# 4_digit_7seg_driver.net
KiCad netlist of a schematic drawn in EAGLE
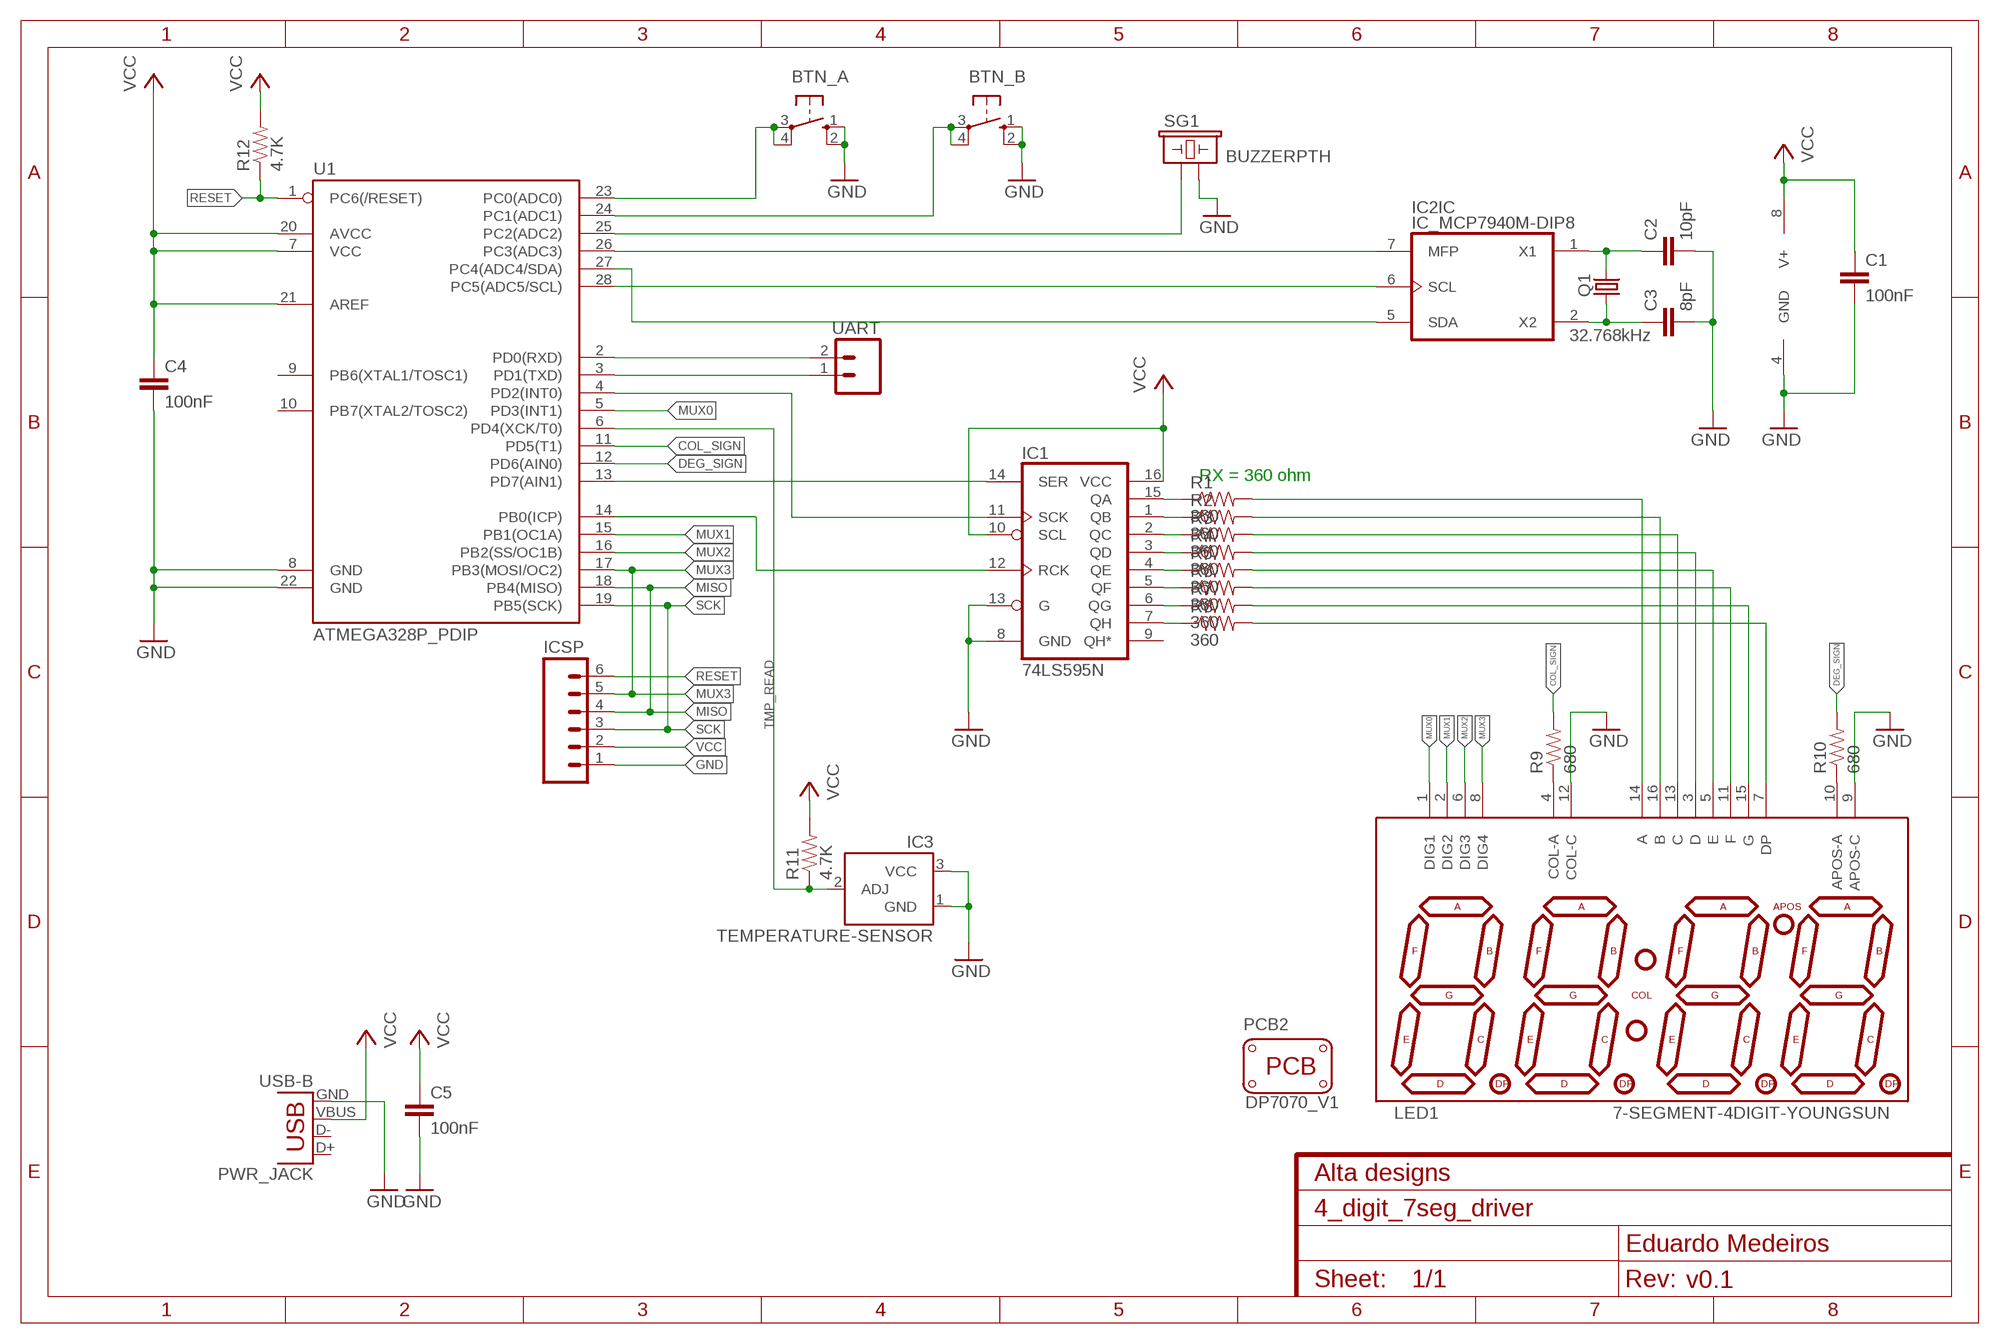
[diagram p0: schematic, sheet 1]

(export (version "E")
  (design (tool "Eeschema 10.0.6"))
  (components
    (comp (ref "BTN_A")
      (value "40-XX")
      (footprint "eagle-import:B3F-40XX")
      (fields (field (name "MF") "OMRON COMPONENTS USA") (field (name "MPN") "B3F-4000"))
      (libsource (lib "eagle-import") (part "40-XX"))
    )
    (comp (ref "BTN_B")
      (value "40-XX")
      (footprint "eagle-import:B3F-40XX")
      (fields (field (name "MF") "OMRON COMPONENTS USA") (field (name "MPN") "B3F-4000"))
      (libsource (lib "eagle-import") (part "40-XX"))
    )
    (comp (ref "C1")
      (value "100nF")
      (footprint "eagle-import:CAP-PTH-5MM")
      (libsource (lib "eagle-import") (part "CAPPTH1"))
    )
    (comp (ref "C2")
      (value "10pF")
      (footprint "eagle-import:CAP-PTH-SMALL")
      (libsource (lib "eagle-import") (part "CAPPTH"))
    )
    (comp (ref "C3")
      (value "8pF")
      (footprint "eagle-import:CAP-PTH-SMALL")
      (libsource (lib "eagle-import") (part "CAPPTH"))
    )
    (comp (ref "C4")
      (value "100nF")
      (footprint "eagle-import:CAP-PTH-5MM")
      (libsource (lib "eagle-import") (part "CAPPTH1"))
    )
    (comp (ref "C5")
      (value "100nF")
      (footprint "eagle-import:CAP-PTH-5MM")
      (libsource (lib "eagle-import") (part "CAPPTH1"))
    )
    (comp (ref "IC1")
      (value "74LS595N")
      (footprint "eagle-import:DIL16")
      (libsource (lib "eagle-import") (part "74595NLS"))
    )
    (comp (ref "IC2")
      (value "IC_MCP7940M-DIP8")
      (footprint "eagle-import:DIP8")
      (libsource (lib "eagle-import") (part "IC_MCP7940M-DIP8"))
    )
    (comp (ref "IC3")
      (value "TEMPERATURE-SENSOR")
      (footprint "eagle-import:TO-92")
      (libsource (lib "eagle-import") (part "TEMPERATURE-SENSOR"))
    )
    (comp (ref "ICSP")
      (value "M06SILK_FEMALE_PTH")
      (footprint "eagle-import:1X06")
      (libsource (lib "eagle-import") (part "M06SILK_FEMALE_PTH"))
    )
    (comp (ref "LED1")
      (value "7-SEGMENT-4DIGIT-YOUNGSUN")
      (footprint "eagle-import:7-SEGMENT-4DIGIT-YOUNGSUN")
      (libsource (lib "eagle-import") (part "7-SEGMENT-4DIGIT-YOUNGSUN"))
    )
    (comp (ref "PCB2")
      (value "PCB_DP_SQUARE-7X7")
      (footprint "eagle-import:DP7070_V1")
      (libsource (lib "eagle-import") (part "PCB_DP_SQUARE-7X7"))
    )
    (comp (ref "PWR_JACK")
      (value "USB-B")
      (footprint "eagle-import:USB-B-PTH")
      (libsource (lib "eagle-import") (part "USBPTH"))
    )
    (comp (ref "Q1")
      (value "32.768kHz")
      (footprint "eagle-import:TC26V")
      (libsource (lib "eagle-import") (part "CRYSTALTC26V"))
    )
    (comp (ref "R1")
      (value "360")
      (footprint "eagle-import:AXIAL-0.1")
      (libsource (lib "eagle-import") (part "RESISTORPTH-1/4W-VERT"))
    )
    (comp (ref "R2")
      (value "360")
      (footprint "eagle-import:AXIAL-0.1")
      (libsource (lib "eagle-import") (part "RESISTORPTH-1/4W-VERT"))
    )
    (comp (ref "R3")
      (value "360")
      (footprint "eagle-import:AXIAL-0.1")
      (libsource (lib "eagle-import") (part "RESISTORPTH-1/4W-VERT"))
    )
    (comp (ref "R4")
      (value "360")
      (footprint "eagle-import:AXIAL-0.1")
      (libsource (lib "eagle-import") (part "RESISTORPTH-1/4W-VERT"))
    )
    (comp (ref "R5")
      (value "360")
      (footprint "eagle-import:AXIAL-0.1")
      (libsource (lib "eagle-import") (part "RESISTORPTH-1/4W-VERT"))
    )
    (comp (ref "R6")
      (value "360")
      (footprint "eagle-import:AXIAL-0.1")
      (libsource (lib "eagle-import") (part "RESISTORPTH-1/4W-VERT"))
    )
    (comp (ref "R7")
      (value "360")
      (footprint "eagle-import:AXIAL-0.1")
      (libsource (lib "eagle-import") (part "RESISTORPTH-1/4W-VERT"))
    )
    (comp (ref "R8")
      (value "360")
      (footprint "eagle-import:AXIAL-0.1")
      (libsource (lib "eagle-import") (part "RESISTORPTH-1/4W-VERT"))
    )
    (comp (ref "R9")
      (value "680")
      (footprint "eagle-import:AXIAL-0.1")
      (libsource (lib "eagle-import") (part "RESISTORPTH-1/4W-VERT"))
    )
    (comp (ref "R10")
      (value "680")
      (footprint "eagle-import:AXIAL-0.1")
      (libsource (lib "eagle-import") (part "RESISTORPTH-1/4W-VERT"))
    )
    (comp (ref "R11")
      (value "4.7K")
      (footprint "eagle-import:AXIAL-0.1")
      (libsource (lib "eagle-import") (part "RESISTORPTH-1/4W-VERT"))
    )
    (comp (ref "R12")
      (value "4.7K")
      (footprint "eagle-import:AXIAL-0.1")
      (libsource (lib "eagle-import") (part "RESISTORPTH-1/4W-VERT"))
    )
    (comp (ref "SG1")
      (value "BUZZERPTH")
      (footprint "eagle-import:BUZZER-12MM")
      (libsource (lib "eagle-import") (part "BUZZERPTH"))
    )
    (comp (ref "U1")
      (value "ATMEGA328P_PDIP")
      (footprint "eagle-import:DIL28-3")
      (libsource (lib "eagle-import") (part "ATMEGA328P_PDIP"))
    )
    (comp (ref "UART")
      (value "M02PTH")
      (footprint "eagle-import:1X02")
      (libsource (lib "eagle-import") (part "M02PTH"))
    )
  )
  (nets
    (net (code "1") (name "/TMP_READ") (class "Default")
      (node (ref "IC3") (pin "2") (pinfunction "ADJ_2") (pintype "bidirectional"))
      (node (ref "R11") (pin "P$1") (pinfunction "1_P$1") (pintype "passive"))
      (node (ref "U1") (pin "6") (pinfunction "PD4(XCK/T0)_6") (pintype "bidirectional"))
    )
    (net (code "2") (name "COL_SIGN") (class "Default")
      (node (ref "R9") (pin "P$2") (pinfunction "2_P$2") (pintype "passive"))
      (node (ref "U1") (pin "11") (pinfunction "PD5(T1)_11") (pintype "bidirectional"))
    )
    (net (code "3") (name "DEG_SIGN") (class "Default")
      (node (ref "R10") (pin "P$2") (pinfunction "2_P$2") (pintype "passive"))
      (node (ref "U1") (pin "12") (pinfunction "PD6(AIN0)_12") (pintype "bidirectional"))
    )
    (net (code "4") (name "GND") (class "Default")
      (node (ref "BTN_A") (pin "1") (pinfunction "S_1") (pintype "passive"))
      (node (ref "BTN_A") (pin "2") (pinfunction "S1_2") (pintype "passive"))
      (node (ref "BTN_B") (pin "1") (pinfunction "S_1") (pintype "passive"))
      (node (ref "BTN_B") (pin "2") (pinfunction "S1_2") (pintype "passive"))
      (node (ref "C1") (pin "2") (pinfunction "2_2") (pintype "passive"))
      (node (ref "C2") (pin "2") (pinfunction "2_2") (pintype "passive"))
      (node (ref "C3") (pin "2") (pinfunction "2_2") (pintype "passive"))
      (node (ref "C4") (pin "2") (pinfunction "2_2") (pintype "passive"))
      (node (ref "C5") (pin "2") (pinfunction "2_2") (pintype "passive"))
      (node (ref "IC1") (pin "13") (pinfunction "G_13") (pintype "input"))
      (node (ref "IC1") (pin "8") (pinfunction "GND_8") (pintype "power_in"))
      (node (ref "IC2") (pin "4") (pinfunction "GND_4") (pintype "power_in"))
      (node (ref "IC3") (pin "1") (pinfunction "GND_1") (pintype "bidirectional"))
      (node (ref "IC3") (pin "3") (pinfunction "VCC_3") (pintype "bidirectional"))
      (node (ref "ICSP") (pin "1") (pinfunction "1_1") (pintype "passive"))
      (node (ref "LED1") (pin "12") (pinfunction "COL-C_12") (pintype "bidirectional"))
      (node (ref "LED1") (pin "9") (pinfunction "APOS-C_9") (pintype "bidirectional"))
      (node (ref "PWR_JACK") (pin "GND") (pinfunction "GND_GND") (pintype "bidirectional"))
      (node (ref "SG1") (pin "-") (pinfunction "2_-") (pintype "passive"))
      (node (ref "U1") (pin "22") (pinfunction "GND_22") (pintype "bidirectional"))
      (node (ref "U1") (pin "8") (pinfunction "GND_8") (pintype "bidirectional"))
    )
    (net (code "5") (name "MISO") (class "Default")
      (node (ref "ICSP") (pin "4") (pinfunction "4_4") (pintype "passive"))
      (node (ref "U1") (pin "18") (pinfunction "PB4(MISO)_18") (pintype "bidirectional"))
    )
    (net (code "6") (name "MUX0") (class "Default")
      (node (ref "LED1") (pin "1") (pinfunction "DIG1_1") (pintype "bidirectional"))
      (node (ref "U1") (pin "5") (pinfunction "PD3(INT1)_5") (pintype "bidirectional"))
    )
    (net (code "7") (name "MUX1") (class "Default")
      (node (ref "LED1") (pin "2") (pinfunction "DIG2_2") (pintype "bidirectional"))
      (node (ref "U1") (pin "15") (pinfunction "PB1(OC1A)_15") (pintype "bidirectional"))
    )
    (net (code "8") (name "MUX2") (class "Default")
      (node (ref "LED1") (pin "6") (pinfunction "DIG3_6") (pintype "bidirectional"))
      (node (ref "U1") (pin "16") (pinfunction "PB2(SS/OC1B)_16") (pintype "bidirectional"))
    )
    (net (code "9") (name "MUX3") (class "Default")
      (node (ref "ICSP") (pin "5") (pinfunction "5_5") (pintype "passive"))
      (node (ref "LED1") (pin "8") (pinfunction "DIG4_8") (pintype "bidirectional"))
      (node (ref "U1") (pin "17") (pinfunction "PB3(MOSI/OC2)_17") (pintype "bidirectional"))
    )
    (net (code "10") (name "Net-(BTN_A-P)") (class "Default")
      (node (ref "BTN_A") (pin "3") (pinfunction "P_3") (pintype "passive"))
      (node (ref "BTN_A") (pin "4") (pinfunction "P1_4") (pintype "passive"))
      (node (ref "U1") (pin "23") (pinfunction "PC0(ADC0)_23") (pintype "bidirectional"))
    )
    (net (code "11") (name "Net-(BTN_B-P)") (class "Default")
      (node (ref "BTN_B") (pin "3") (pinfunction "P_3") (pintype "passive"))
      (node (ref "BTN_B") (pin "4") (pinfunction "P1_4") (pintype "passive"))
      (node (ref "U1") (pin "24") (pinfunction "PC1(ADC1)_24") (pintype "bidirectional"))
    )
    (net (code "12") (name "Net-(IC1-QA)") (class "Default")
      (node (ref "IC1") (pin "15") (pinfunction "QA_15") (pintype "tri_state"))
      (node (ref "R1") (pin "P$1") (pinfunction "1_P$1") (pintype "passive"))
    )
    (net (code "13") (name "Net-(IC1-QB)") (class "Default")
      (node (ref "IC1") (pin "1") (pinfunction "QB_1") (pintype "tri_state"))
      (node (ref "R2") (pin "P$1") (pinfunction "1_P$1") (pintype "passive"))
    )
    (net (code "14") (name "Net-(IC1-QC)") (class "Default")
      (node (ref "IC1") (pin "2") (pinfunction "QC_2") (pintype "tri_state"))
      (node (ref "R3") (pin "P$1") (pinfunction "1_P$1") (pintype "passive"))
    )
    (net (code "15") (name "Net-(IC1-QD)") (class "Default")
      (node (ref "IC1") (pin "3") (pinfunction "QD_3") (pintype "tri_state"))
      (node (ref "R4") (pin "P$1") (pinfunction "1_P$1") (pintype "passive"))
    )
    (net (code "16") (name "Net-(IC1-QE)") (class "Default")
      (node (ref "IC1") (pin "4") (pinfunction "QE_4") (pintype "tri_state"))
      (node (ref "R5") (pin "P$1") (pinfunction "1_P$1") (pintype "passive"))
    )
    (net (code "17") (name "Net-(IC1-QF)") (class "Default")
      (node (ref "IC1") (pin "5") (pinfunction "QF_5") (pintype "tri_state"))
      (node (ref "R6") (pin "P$1") (pinfunction "1_P$1") (pintype "passive"))
    )
    (net (code "18") (name "Net-(IC1-QG)") (class "Default")
      (node (ref "IC1") (pin "6") (pinfunction "QG_6") (pintype "tri_state"))
      (node (ref "R7") (pin "P$1") (pinfunction "1_P$1") (pintype "passive"))
    )
    (net (code "19") (name "Net-(IC1-QH)") (class "Default")
      (node (ref "IC1") (pin "7") (pinfunction "QH_7") (pintype "tri_state"))
      (node (ref "R8") (pin "P$1") (pinfunction "1_P$1") (pintype "passive"))
    )
    (net (code "20") (name "Net-(IC1-RCK)") (class "Default")
      (node (ref "IC1") (pin "12") (pinfunction "RCK_12") (pintype "input"))
      (node (ref "U1") (pin "14") (pinfunction "PB0(ICP)_14") (pintype "bidirectional"))
    )
    (net (code "21") (name "Net-(IC1-SCK)") (class "Default")
      (node (ref "IC1") (pin "11") (pinfunction "SCK_11") (pintype "input"))
      (node (ref "U1") (pin "4") (pinfunction "PD2(INT0)_4") (pintype "bidirectional"))
    )
    (net (code "22") (name "Net-(IC1-SER)") (class "Default")
      (node (ref "IC1") (pin "14") (pinfunction "SER_14") (pintype "input"))
      (node (ref "U1") (pin "13") (pinfunction "PD7(AIN1)_13") (pintype "bidirectional"))
    )
    (net (code "23") (name "Net-(IC2A-MFP)") (class "Default")
      (node (ref "IC2") (pin "7") (pinfunction "MFP_7") (pintype "bidirectional"))
      (node (ref "U1") (pin "26") (pinfunction "PC3(ADC3)_26") (pintype "bidirectional"))
    )
    (net (code "24") (name "Net-(IC2A-SCL)") (class "Default")
      (node (ref "IC2") (pin "6") (pinfunction "SCL_6") (pintype "input"))
      (node (ref "U1") (pin "28") (pinfunction "PC5(ADC5/SCL)_28") (pintype "bidirectional"))
    )
    (net (code "25") (name "Net-(IC2A-SDA)") (class "Default")
      (node (ref "IC2") (pin "5") (pinfunction "SDA_5") (pintype "bidirectional"))
      (node (ref "U1") (pin "27") (pinfunction "PC4(ADC4/SDA)_27") (pintype "bidirectional"))
    )
    (net (code "26") (name "Net-(IC2A-X1)") (class "Default")
      (node (ref "C2") (pin "1") (pinfunction "1_1") (pintype "passive"))
      (node (ref "IC2") (pin "1") (pinfunction "X1_1") (pintype "input"))
      (node (ref "Q1") (pin "2") (pinfunction "2_2") (pintype "passive"))
    )
    (net (code "27") (name "Net-(IC2A-X2)") (class "Default")
      (node (ref "C3") (pin "1") (pinfunction "1_1") (pintype "passive"))
      (node (ref "IC2") (pin "2") (pinfunction "X2_2") (pintype "output"))
      (node (ref "Q1") (pin "1") (pinfunction "1_1") (pintype "passive"))
    )
    (net (code "28") (name "Net-(LED1-A)") (class "Default")
      (node (ref "LED1") (pin "14") (pinfunction "A_14") (pintype "bidirectional"))
      (node (ref "R1") (pin "P$2") (pinfunction "2_P$2") (pintype "passive"))
    )
    (net (code "29") (name "Net-(LED1-APOS-A)") (class "Default")
      (node (ref "LED1") (pin "10") (pinfunction "APOS-A_10") (pintype "bidirectional"))
      (node (ref "R10") (pin "P$1") (pinfunction "1_P$1") (pintype "passive"))
    )
    (net (code "30") (name "Net-(LED1-B)") (class "Default")
      (node (ref "LED1") (pin "16") (pinfunction "B_16") (pintype "bidirectional"))
      (node (ref "R2") (pin "P$2") (pinfunction "2_P$2") (pintype "passive"))
    )
    (net (code "31") (name "Net-(LED1-C)") (class "Default")
      (node (ref "LED1") (pin "13") (pinfunction "C_13") (pintype "bidirectional"))
      (node (ref "R3") (pin "P$2") (pinfunction "2_P$2") (pintype "passive"))
    )
    (net (code "32") (name "Net-(LED1-COL-A)") (class "Default")
      (node (ref "LED1") (pin "4") (pinfunction "COL-A_4") (pintype "bidirectional"))
      (node (ref "R9") (pin "P$1") (pinfunction "1_P$1") (pintype "passive"))
    )
    (net (code "33") (name "Net-(LED1-D)") (class "Default")
      (node (ref "LED1") (pin "3") (pinfunction "D_3") (pintype "bidirectional"))
      (node (ref "R4") (pin "P$2") (pinfunction "2_P$2") (pintype "passive"))
    )
    (net (code "34") (name "Net-(LED1-DP)") (class "Default")
      (node (ref "LED1") (pin "7") (pinfunction "DP_7") (pintype "bidirectional"))
      (node (ref "R8") (pin "P$2") (pinfunction "2_P$2") (pintype "passive"))
    )
    (net (code "35") (name "Net-(LED1-E)") (class "Default")
      (node (ref "LED1") (pin "5") (pinfunction "E_5") (pintype "bidirectional"))
      (node (ref "R5") (pin "P$2") (pinfunction "2_P$2") (pintype "passive"))
    )
    (net (code "36") (name "Net-(LED1-F)") (class "Default")
      (node (ref "LED1") (pin "11") (pinfunction "F_11") (pintype "bidirectional"))
      (node (ref "R6") (pin "P$2") (pinfunction "2_P$2") (pintype "passive"))
    )
    (net (code "37") (name "Net-(LED1-G)") (class "Default")
      (node (ref "LED1") (pin "15") (pinfunction "G_15") (pintype "bidirectional"))
      (node (ref "R7") (pin "P$2") (pinfunction "2_P$2") (pintype "passive"))
    )
    (net (code "38") (name "Net-(SG1-1)") (class "Default")
      (node (ref "SG1") (pin "+") (pinfunction "1_+") (pintype "passive"))
      (node (ref "U1") (pin "25") (pinfunction "PC2(ADC2)_25") (pintype "bidirectional"))
    )
    (net (code "39") (name "Net-(U1-PD0(RXD))") (class "Default")
      (node (ref "U1") (pin "2") (pinfunction "PD0(RXD)_2") (pintype "bidirectional"))
      (node (ref "UART") (pin "2") (pinfunction "2_2") (pintype "passive"))
    )
    (net (code "40") (name "Net-(U1-PD1(TXD))") (class "Default")
      (node (ref "U1") (pin "3") (pinfunction "PD1(TXD)_3") (pintype "bidirectional"))
      (node (ref "UART") (pin "1") (pinfunction "1_1") (pintype "passive"))
    )
    (net (code "41") (name "RESET") (class "Default")
      (node (ref "ICSP") (pin "6") (pinfunction "6_6") (pintype "passive"))
      (node (ref "R12") (pin "P$1") (pinfunction "1_P$1") (pintype "passive"))
      (node (ref "U1") (pin "1") (pinfunction "PC6(/RESET)_1") (pintype "bidirectional"))
    )
    (net (code "42") (name "SCK") (class "Default")
      (node (ref "ICSP") (pin "3") (pinfunction "3_3") (pintype "passive"))
      (node (ref "U1") (pin "19") (pinfunction "PB5(SCK)_19") (pintype "bidirectional"))
    )
    (net (code "43") (name "VCC") (class "Default")
      (node (ref "C1") (pin "1") (pinfunction "1_1") (pintype "passive"))
      (node (ref "C4") (pin "1") (pinfunction "1_1") (pintype "passive"))
      (node (ref "C5") (pin "1") (pinfunction "1_1") (pintype "passive"))
      (node (ref "IC1") (pin "10") (pinfunction "SCL_10") (pintype "input"))
      (node (ref "IC1") (pin "16") (pinfunction "VCC_16") (pintype "power_in"))
      (node (ref "IC2") (pin "8") (pinfunction "V+_8") (pintype "power_in"))
      (node (ref "ICSP") (pin "2") (pinfunction "2_2") (pintype "passive"))
      (node (ref "PWR_JACK") (pin "VBUS") (pinfunction "VBUS_VBUS") (pintype "bidirectional"))
      (node (ref "R11") (pin "P$2") (pinfunction "2_P$2") (pintype "passive"))
      (node (ref "R12") (pin "P$2") (pinfunction "2_P$2") (pintype "passive"))
      (node (ref "U1") (pin "20") (pinfunction "AVCC_20") (pintype "bidirectional"))
      (node (ref "U1") (pin "21") (pinfunction "AREF_21") (pintype "bidirectional"))
      (node (ref "U1") (pin "7") (pinfunction "VCC_7") (pintype "bidirectional"))
    )
    (net (code "44") (name "unconnected-(IC1-QH*-Pad9)") (class "Default")
      (node (ref "IC1") (pin "9") (pinfunction "QH*_9") (pintype "tri_state"))
    )
    (net (code "45") (name "unconnected-(PWR_JACK-PadD+)") (class "Default")
      (node (ref "PWR_JACK") (pin "D+") (pinfunction "D+_D+") (pintype "bidirectional"))
    )
    (net (code "46") (name "unconnected-(PWR_JACK-PadD-)") (class "Default")
      (node (ref "PWR_JACK") (pin "D-") (pinfunction "D-_D-") (pintype "bidirectional"))
    )
    (net (code "47") (name "unconnected-(U1-PB6(XTAL1{slash}TOSC1)-Pad9)") (class "Default")
      (node (ref "U1") (pin "9") (pinfunction "PB6(XTAL1/TOSC1)_9") (pintype "bidirectional"))
    )
    (net (code "48") (name "unconnected-(U1-PB7(XTAL2{slash}TOSC2)-Pad10)") (class "Default")
      (node (ref "U1") (pin "10") (pinfunction "PB7(XTAL2/TOSC2)_10") (pintype "bidirectional"))
    )
  )
)
